# SNES_RGBAmp_wCSYNC_SVid.net
KiCad netlist of a schematic drawn in EAGLE
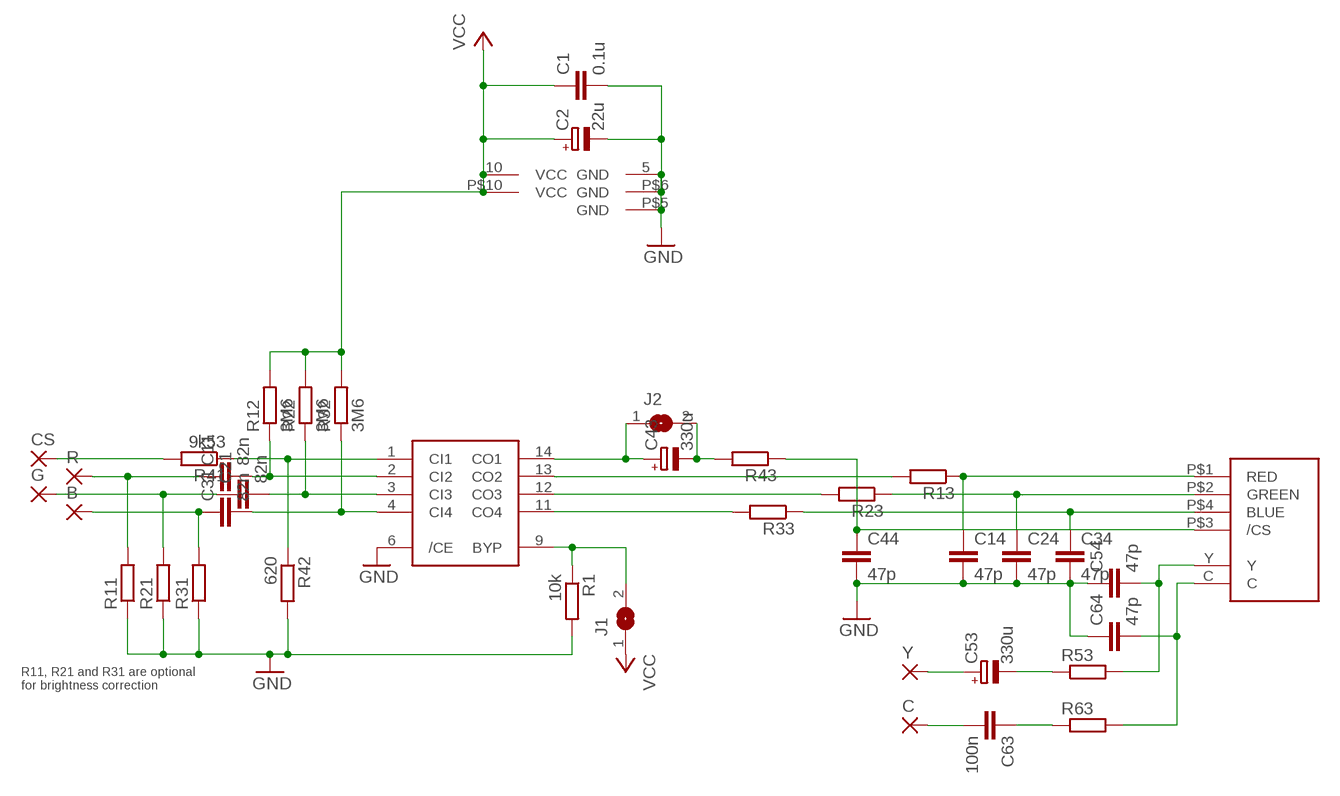
[diagram p0: schematic, sheet 1]

(export (version "E")
  (design (tool "Eeschema 10.0.6"))
  (components
    (comp (ref "B")
      (value "SMD2")
      (footprint "eagle-import:SMD1,27-2,54")
      (libsource (lib "eagle-import") (part "SMD2"))
    )
    (comp (ref "C")
      (value "SMD2")
      (footprint "eagle-import:SMD1,27-2,54")
      (libsource (lib "eagle-import") (part "SMD2"))
    )
    (comp (ref "C1")
      (value "0.1u")
      (footprint "eagle-import:C0603K")
      (libsource (lib "eagle-import") (part "C-EUC0603K"))
    )
    (comp (ref "C2")
      (value "22u")
      (footprint "eagle-import:SMC_B")
      (libsource (lib "eagle-import") (part "CPOL-EUSMCB"))
    )
    (comp (ref "C11")
      (value "82n")
      (footprint "eagle-import:C0603K")
      (libsource (lib "eagle-import") (part "C-EUC0603K"))
    )
    (comp (ref "C14")
      (value "47p")
      (footprint "eagle-import:C0603K")
      (libsource (lib "eagle-import") (part "C-EUC0603K"))
    )
    (comp (ref "C21")
      (value "82n")
      (footprint "eagle-import:C0603K")
      (libsource (lib "eagle-import") (part "C-EUC0603K"))
    )
    (comp (ref "C24")
      (value "47p")
      (footprint "eagle-import:C0603K")
      (libsource (lib "eagle-import") (part "C-EUC0603K"))
    )
    (comp (ref "C31")
      (value "82n")
      (footprint "eagle-import:C0603K")
      (libsource (lib "eagle-import") (part "C-EUC0603K"))
    )
    (comp (ref "C34")
      (value "47p")
      (footprint "eagle-import:C0603K")
      (libsource (lib "eagle-import") (part "C-EUC0603K"))
    )
    (comp (ref "C43")
      (value "330u")
      (footprint "eagle-import:SMC_D")
      (libsource (lib "eagle-import") (part "CPOL-EUSMCD"))
    )
    (comp (ref "C44")
      (value "47p")
      (footprint "eagle-import:C0603K")
      (libsource (lib "eagle-import") (part "C-EUC0603K"))
    )
    (comp (ref "C53")
      (value "330u")
      (footprint "eagle-import:SMC_D")
      (libsource (lib "eagle-import") (part "CPOL-EUSMCD"))
    )
    (comp (ref "C54")
      (value "47p")
      (footprint "eagle-import:C0603K")
      (libsource (lib "eagle-import") (part "C-EUC0603K"))
    )
    (comp (ref "C63")
      (value "100n")
      (footprint "eagle-import:C0603K")
      (libsource (lib "eagle-import") (part "C-EUC0603K"))
    )
    (comp (ref "C64")
      (value "47p")
      (footprint "eagle-import:C0603K")
      (libsource (lib "eagle-import") (part "C-EUC0603K"))
    )
    (comp (ref "CS")
      (value "SMD2")
      (footprint "eagle-import:SMD1,27-2,54")
      (libsource (lib "eagle-import") (part "SMD2"))
    )
    (comp (ref "G")
      (value "SMD2")
      (footprint "eagle-import:SMD1,27-2,54")
      (libsource (lib "eagle-import") (part "SMD2"))
    )
    (comp (ref "J1") (value "SJ") (footprint "eagle-import:SJ") (libsource (lib "eagle-import") (part "SJ")))
    (comp (ref "J2") (value "SJ") (footprint "eagle-import:SJ") (libsource (lib "eagle-import") (part "SJ")))
    (comp (ref "R")
      (value "SMD2")
      (footprint "eagle-import:SMD1,27-2,54")
      (libsource (lib "eagle-import") (part "SMD2"))
    )
    (comp (ref "R1")
      (value "10k")
      (footprint "eagle-import:R0603")
      (libsource (lib "eagle-import") (part "R-EU_R0603"))
    )
    (comp (ref "R11")
      (value "R-EU_R0603")
      (footprint "eagle-import:R0603")
      (libsource (lib "eagle-import") (part "R-EU_R0603"))
    )
    (comp (ref "R12")
      (value "3M6")
      (footprint "eagle-import:R0603")
      (libsource (lib "eagle-import") (part "R-EU_R0603"))
    )
    (comp (ref "R13")
      (value "R-EU_R0603")
      (footprint "eagle-import:R0603")
      (libsource (lib "eagle-import") (part "R-EU_R0603"))
    )
    (comp (ref "R21")
      (value "R-EU_R0603")
      (footprint "eagle-import:R0603")
      (libsource (lib "eagle-import") (part "R-EU_R0603"))
    )
    (comp (ref "R22")
      (value "3M6")
      (footprint "eagle-import:R0603")
      (libsource (lib "eagle-import") (part "R-EU_R0603"))
    )
    (comp (ref "R23")
      (value "R-EU_R0603")
      (footprint "eagle-import:R0603")
      (libsource (lib "eagle-import") (part "R-EU_R0603"))
    )
    (comp (ref "R31")
      (value "R-EU_R0603")
      (footprint "eagle-import:R0603")
      (libsource (lib "eagle-import") (part "R-EU_R0603"))
    )
    (comp (ref "R32")
      (value "3M6")
      (footprint "eagle-import:R0603")
      (libsource (lib "eagle-import") (part "R-EU_R0603"))
    )
    (comp (ref "R33")
      (value "R-EU_R0603")
      (footprint "eagle-import:R0603")
      (libsource (lib "eagle-import") (part "R-EU_R0603"))
    )
    (comp (ref "R41")
      (value "9k53")
      (footprint "eagle-import:R0603")
      (libsource (lib "eagle-import") (part "R-EU_R0603"))
    )
    (comp (ref "R42")
      (value "620")
      (footprint "eagle-import:R0603")
      (libsource (lib "eagle-import") (part "R-EU_R0603"))
    )
    (comp (ref "R43")
      (value "R-EU_R0603")
      (footprint "eagle-import:R0603")
      (libsource (lib "eagle-import") (part "R-EU_R0603"))
    )
    (comp (ref "R53")
      (value "R-EU_R0603")
      (footprint "eagle-import:R0603")
      (libsource (lib "eagle-import") (part "R-EU_R0603"))
    )
    (comp (ref "R63")
      (value "R-EU_R0603")
      (footprint "eagle-import:R0603")
      (libsource (lib "eagle-import") (part "R-EU_R0603"))
    )
    (comp (ref "U$1")
      (value "SNES_MULTIAV_RGBSYC")
      (footprint "eagle-import:SNES_MULTIAV_RGBSYC")
      (libsource (lib "eagle-import") (part "SNES_MULTIAV_RGBSYC"))
    )
    (comp (ref "U1")
      (value "THS7374")
      (footprint "eagle-import:THS7374")
      (libsource (lib "eagle-import") (part "THS7374"))
    )
    (comp (ref "Y")
      (value "SMD2")
      (footprint "eagle-import:SMD1,27-2,54")
      (libsource (lib "eagle-import") (part "SMD2"))
    )
  )
  (nets
    (net (code "1") (name "GND") (class "Default")
      (node (ref "C1") (pin "2") (pinfunction "2_2") (pintype "passive"))
      (node (ref "C14") (pin "2") (pinfunction "2_2") (pintype "passive"))
      (node (ref "C2") (pin "-") (pinfunction "-_-") (pintype "passive"))
      (node (ref "C24") (pin "2") (pinfunction "2_2") (pintype "passive"))
      (node (ref "C34") (pin "2") (pinfunction "2_2") (pintype "passive"))
      (node (ref "C44") (pin "2") (pinfunction "2_2") (pintype "passive"))
      (node (ref "C54") (pin "1") (pinfunction "1_1") (pintype "passive"))
      (node (ref "C64") (pin "1") (pinfunction "1_1") (pintype "passive"))
      (node (ref "R1") (pin "2") (pinfunction "2_2") (pintype "passive"))
      (node (ref "R11") (pin "1") (pinfunction "1_1") (pintype "passive"))
      (node (ref "R21") (pin "1") (pinfunction "1_1") (pintype "passive"))
      (node (ref "R31") (pin "1") (pinfunction "1_1") (pintype "passive"))
      (node (ref "R42") (pin "2") (pinfunction "2_2") (pintype "passive"))
      (node (ref "U$1") (pin "P$5") (pinfunction "GND_P$5") (pintype "bidirectional"))
      (node (ref "U$1") (pin "P$6") (pinfunction "GND_P$6") (pintype "bidirectional"))
      (node (ref "U1") (pin "5") (pinfunction "GND_5") (pintype "bidirectional"))
      (node (ref "U1") (pin "6") (pinfunction "/CE_6") (pintype "bidirectional"))
    )
    (net (code "2") (name "Net-(B-P)") (class "Default")
      (node (ref "B") (pin "1") (pinfunction "P_1") (pintype "passive"))
      (node (ref "C31") (pin "1") (pinfunction "1_1") (pintype "passive"))
      (node (ref "R31") (pin "2") (pinfunction "2_2") (pintype "passive"))
    )
    (net (code "3") (name "Net-(C-P)") (class "Default")
      (node (ref "C") (pin "1") (pinfunction "P_1") (pintype "passive"))
      (node (ref "C63") (pin "2") (pinfunction "2_2") (pintype "passive"))
    )
    (net (code "4") (name "Net-(C43-Pad-)") (class "Default")
      (node (ref "C43") (pin "-") (pinfunction "-_-") (pintype "passive"))
      (node (ref "J2") (pin "2") (pinfunction "2_2") (pintype "passive"))
      (node (ref "R43") (pin "2") (pinfunction "2_2") (pintype "passive"))
    )
    (net (code "5") (name "Net-(C53-Pad-)") (class "Default")
      (node (ref "C53") (pin "-") (pinfunction "-_-") (pintype "passive"))
      (node (ref "R53") (pin "1") (pinfunction "1_1") (pintype "passive"))
    )
    (net (code "6") (name "Net-(C54-Pad2)") (class "Default")
      (node (ref "C54") (pin "2") (pinfunction "2_2") (pintype "passive"))
      (node (ref "R53") (pin "2") (pinfunction "2_2") (pintype "passive"))
      (node (ref "U$1") (pin "Y") (pinfunction "Y_Y") (pintype "bidirectional"))
    )
    (net (code "7") (name "Net-(C63-Pad1)") (class "Default")
      (node (ref "C63") (pin "1") (pinfunction "1_1") (pintype "passive"))
      (node (ref "R63") (pin "1") (pinfunction "1_1") (pintype "passive"))
    )
    (net (code "8") (name "Net-(C64-Pad2)") (class "Default")
      (node (ref "C64") (pin "2") (pinfunction "2_2") (pintype "passive"))
      (node (ref "R63") (pin "2") (pinfunction "2_2") (pintype "passive"))
      (node (ref "U$1") (pin "C") (pinfunction "C_C") (pintype "bidirectional"))
    )
    (net (code "9") (name "Net-(CS-P)") (class "Default")
      (node (ref "CS") (pin "1") (pinfunction "P_1") (pintype "passive"))
      (node (ref "R41") (pin "2") (pinfunction "2_2") (pintype "passive"))
    )
    (net (code "10") (name "Net-(G-P)") (class "Default")
      (node (ref "C21") (pin "1") (pinfunction "1_1") (pintype "passive"))
      (node (ref "G") (pin "1") (pinfunction "P_1") (pintype "passive"))
      (node (ref "R21") (pin "2") (pinfunction "2_2") (pintype "passive"))
    )
    (net (code "11") (name "Net-(R-P)") (class "Default")
      (node (ref "C11") (pin "1") (pinfunction "1_1") (pintype "passive"))
      (node (ref "R") (pin "1") (pinfunction "P_1") (pintype "passive"))
      (node (ref "R11") (pin "2") (pinfunction "2_2") (pintype "passive"))
    )
    (net (code "12") (name "Net-(U$1A-BLUE)") (class "Default")
      (node (ref "C34") (pin "1") (pinfunction "1_1") (pintype "passive"))
      (node (ref "R33") (pin "1") (pinfunction "1_1") (pintype "passive"))
      (node (ref "U$1") (pin "P$4") (pinfunction "BLUE_P$4") (pintype "bidirectional"))
    )
    (net (code "13") (name "Net-(U$1A-GREEN)") (class "Default")
      (node (ref "C24") (pin "1") (pinfunction "1_1") (pintype "passive"))
      (node (ref "R23") (pin "1") (pinfunction "1_1") (pintype "passive"))
      (node (ref "U$1") (pin "P$2") (pinfunction "GREEN_P$2") (pintype "bidirectional"))
    )
    (net (code "14") (name "Net-(U$1A-RED)") (class "Default")
      (node (ref "C14") (pin "1") (pinfunction "1_1") (pintype "passive"))
      (node (ref "R13") (pin "1") (pinfunction "1_1") (pintype "passive"))
      (node (ref "U$1") (pin "P$1") (pinfunction "RED_P$1") (pintype "bidirectional"))
    )
    (net (code "15") (name "Net-(U$1A-{slash}CS)") (class "Default")
      (node (ref "C44") (pin "1") (pinfunction "1_1") (pintype "passive"))
      (node (ref "R43") (pin "1") (pinfunction "1_1") (pintype "passive"))
      (node (ref "U$1") (pin "P$3") (pinfunction "/CS_P$3") (pintype "bidirectional"))
    )
    (net (code "16") (name "Net-(U1A-BYP)") (class "Default")
      (node (ref "J1") (pin "2") (pinfunction "2_2") (pintype "passive"))
      (node (ref "R1") (pin "1") (pinfunction "1_1") (pintype "passive"))
      (node (ref "U1") (pin "9") (pinfunction "BYP_9") (pintype "bidirectional"))
    )
    (net (code "17") (name "Net-(U1A-CI1)") (class "Default")
      (node (ref "R41") (pin "1") (pinfunction "1_1") (pintype "passive"))
      (node (ref "R42") (pin "1") (pinfunction "1_1") (pintype "passive"))
      (node (ref "U1") (pin "1") (pinfunction "CI1_1") (pintype "bidirectional"))
    )
    (net (code "18") (name "Net-(U1A-CI2)") (class "Default")
      (node (ref "C11") (pin "2") (pinfunction "2_2") (pintype "passive"))
      (node (ref "R12") (pin "1") (pinfunction "1_1") (pintype "passive"))
      (node (ref "U1") (pin "2") (pinfunction "CI2_2") (pintype "bidirectional"))
    )
    (net (code "19") (name "Net-(U1A-CI3)") (class "Default")
      (node (ref "C21") (pin "2") (pinfunction "2_2") (pintype "passive"))
      (node (ref "R22") (pin "1") (pinfunction "1_1") (pintype "passive"))
      (node (ref "U1") (pin "3") (pinfunction "CI3_3") (pintype "bidirectional"))
    )
    (net (code "20") (name "Net-(U1A-CI4)") (class "Default")
      (node (ref "C31") (pin "2") (pinfunction "2_2") (pintype "passive"))
      (node (ref "R32") (pin "1") (pinfunction "1_1") (pintype "passive"))
      (node (ref "U1") (pin "4") (pinfunction "CI4_4") (pintype "bidirectional"))
    )
    (net (code "21") (name "Net-(U1A-CO1)") (class "Default")
      (node (ref "C43") (pin "+") (pinfunction "+_+") (pintype "passive"))
      (node (ref "J2") (pin "1") (pinfunction "1_1") (pintype "passive"))
      (node (ref "U1") (pin "14") (pinfunction "CO1_14") (pintype "bidirectional"))
    )
    (net (code "22") (name "Net-(U1A-CO2)") (class "Default")
      (node (ref "R13") (pin "2") (pinfunction "2_2") (pintype "passive"))
      (node (ref "U1") (pin "13") (pinfunction "CO2_13") (pintype "bidirectional"))
    )
    (net (code "23") (name "Net-(U1A-CO3)") (class "Default")
      (node (ref "R23") (pin "2") (pinfunction "2_2") (pintype "passive"))
      (node (ref "U1") (pin "12") (pinfunction "CO3_12") (pintype "bidirectional"))
    )
    (net (code "24") (name "Net-(U1A-CO4)") (class "Default")
      (node (ref "R33") (pin "2") (pinfunction "2_2") (pintype "passive"))
      (node (ref "U1") (pin "11") (pinfunction "CO4_11") (pintype "bidirectional"))
    )
    (net (code "25") (name "Net-(Y-P)") (class "Default")
      (node (ref "C53") (pin "+") (pinfunction "+_+") (pintype "passive"))
      (node (ref "Y") (pin "1") (pinfunction "P_1") (pintype "passive"))
    )
    (net (code "26") (name "VCC") (class "Default")
      (node (ref "C1") (pin "1") (pinfunction "1_1") (pintype "passive"))
      (node (ref "C2") (pin "+") (pinfunction "+_+") (pintype "passive"))
      (node (ref "J1") (pin "1") (pinfunction "1_1") (pintype "passive"))
      (node (ref "R12") (pin "2") (pinfunction "2_2") (pintype "passive"))
      (node (ref "R22") (pin "2") (pinfunction "2_2") (pintype "passive"))
      (node (ref "R32") (pin "2") (pinfunction "2_2") (pintype "passive"))
      (node (ref "U$1") (pin "P$10") (pinfunction "VCC_P$10") (pintype "bidirectional"))
      (node (ref "U1") (pin "10") (pinfunction "VCC_10") (pintype "bidirectional"))
    )
  )
)
